# Magnetophon.net
KiCad netlist of a schematic drawn in EAGLE
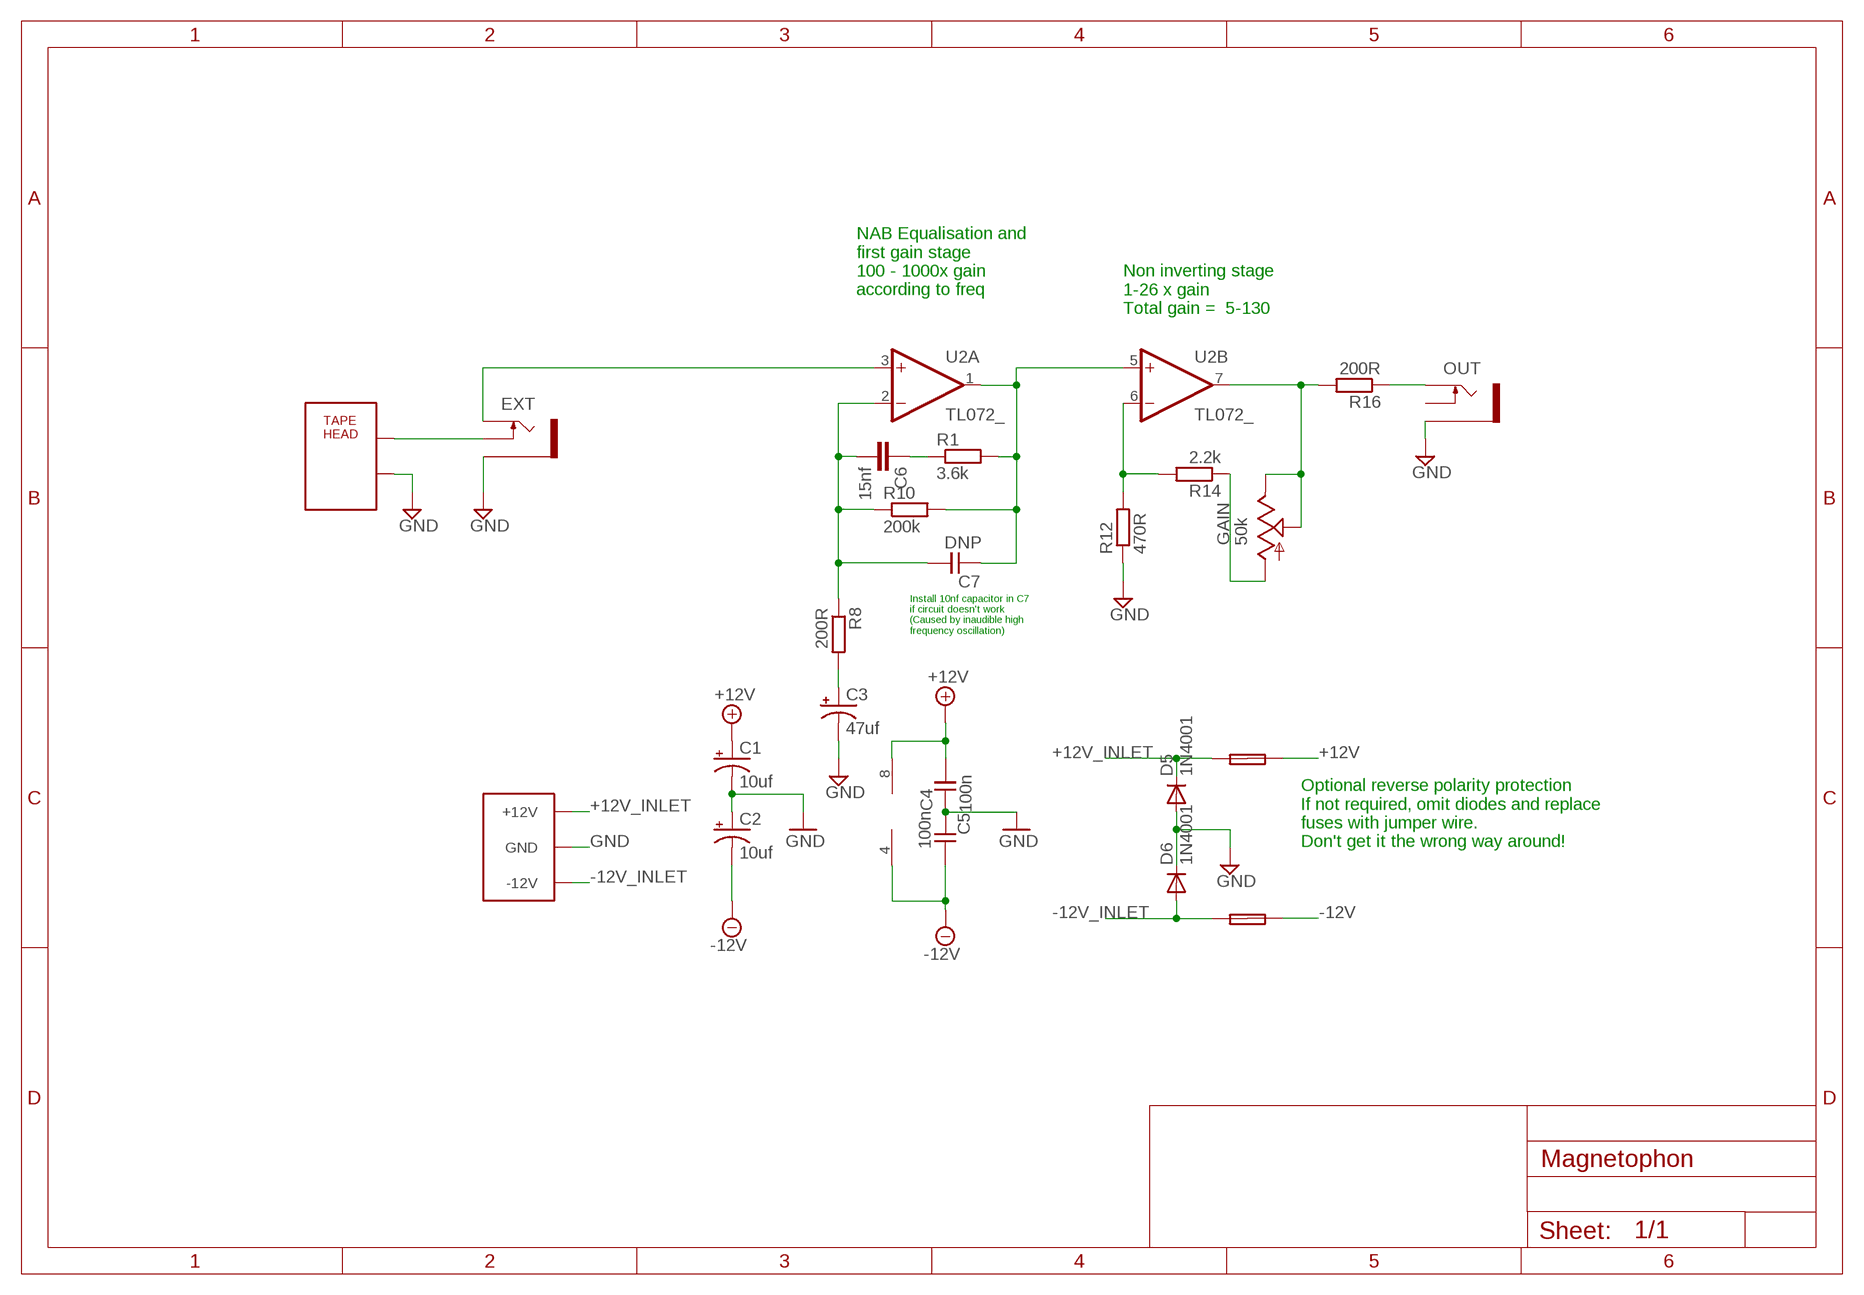
[diagram p0: schematic, sheet 1]

(export (version "E")
  (design (tool "Eeschema 10.0.6"))
  (components
    (comp (ref "1")
      (value "FUSE")
      (footprint "eagle-import:C050H075X075")
      (libsource (lib "eagle-import") (part "PTC_FUSEPOLY_FUSE"))
    )
    (comp (ref "C1")
      (value "10uf")
      (footprint "eagle-import:CPOL-RADIAL-10UF-25V")
      (libsource (lib "eagle-import") (part "CAP_POLPTH2"))
    )
    (comp (ref "C2")
      (value "10uf")
      (footprint "eagle-import:CPOL-RADIAL-10UF-25V")
      (libsource (lib "eagle-import") (part "CAP_POLPTH2"))
    )
    (comp (ref "C3")
      (value "47uf")
      (footprint "eagle-import:CPOL-RADIAL-10UF-25V")
      (libsource (lib "eagle-import") (part "CAP_POLPTH2"))
    )
    (comp (ref "C4")
      (value "100n")
      (footprint "eagle-import:C050-024X044")
      (libsource (lib "eagle-import") (part "C-EU050-024X044"))
    )
    (comp (ref "C5")
      (value "100n")
      (footprint "eagle-import:C050-024X044")
      (libsource (lib "eagle-import") (part "C-EU050-024X044"))
    )
    (comp (ref "C6")
      (value "15nf")
      (footprint "eagle-import:C050-030X075")
      (libsource (lib "eagle-import") (part "rcl_C-EU050-030X075"))
    )
    (comp (ref "C7")
      (value "DNP")
      (footprint "eagle-import:C050-024X044")
      (libsource (lib "eagle-import") (part "C-EU050-024X044"))
    )
    (comp (ref "D5")
      (value "1N4001")
      (footprint "eagle-import:DO41-10")
      (libsource (lib "eagle-import") (part "1N4004"))
    )
    (comp (ref "D6")
      (value "1N4001")
      (footprint "eagle-import:DO41-10")
      (libsource (lib "eagle-import") (part "1N4004"))
    )
    (comp (ref "EXT")
      (value "THONKICONNNEW")
      (footprint "eagle-import:WQP-PJ301M-12_JACK")
      (libsource (lib "eagle-import") (part "THONKICONNNEW"))
    )
    (comp (ref "FUSE")
      (value "FUSE")
      (footprint "eagle-import:C050H075X075")
      (libsource (lib "eagle-import") (part "PTC_FUSEPOLY_FUSE"))
    )
    (comp (ref "GAIN")
      (value "50k")
      (footprint "eagle-import:EVUF")
      (libsource (lib "eagle-import") (part "ALPHA-9MMAF2"))
    )
    (comp (ref "OUT")
      (value "THONKICONNNEW")
      (footprint "eagle-import:WQP-PJ301M-12_JACK")
      (libsource (lib "eagle-import") (part "THONKICONNNEW"))
    )
    (comp (ref "R1")
      (value "3.6k")
      (footprint "eagle-import:7MM_RESISTOR")
      (libsource (lib "eagle-import") (part "RESISTOR7MM"))
    )
    (comp (ref "R8")
      (value "200R")
      (footprint "eagle-import:7MM_RESISTOR")
      (libsource (lib "eagle-import") (part "RESISTOR7MM"))
    )
    (comp (ref "R10")
      (value "200k")
      (footprint "eagle-import:7MM_RESISTOR")
      (libsource (lib "eagle-import") (part "RESISTOR7MM"))
    )
    (comp (ref "R12")
      (value "470R")
      (footprint "eagle-import:7MM_RESISTOR")
      (libsource (lib "eagle-import") (part "RESISTOR7MM"))
    )
    (comp (ref "R14")
      (value "2.2k")
      (footprint "eagle-import:7MM_RESISTOR")
      (libsource (lib "eagle-import") (part "RESISTOR7MM"))
    )
    (comp (ref "R16")
      (value "200R")
      (footprint "eagle-import:7MM_RESISTOR")
      (libsource (lib "eagle-import") (part "RESISTOR7MM"))
    )
    (comp (ref "U$1")
      (value "MONO_CASSETTE_HEAD")
      (footprint "eagle-import:MONO_CASSETTE_HEAD")
      (libsource (lib "eagle-import") (part "MONO_CASSETTE_HEAD"))
    )
    (comp (ref "U$2")
      (value "EURO_POWER_LOCK")
      (footprint "eagle-import:EURO_PWR_HEADER_LOCK")
      (libsource (lib "eagle-import") (part "EURO_POWER_LOCK"))
    )
    (comp (ref "U2")
      (value "TL072_")
      (footprint "eagle-import:DIL08")
      (libsource (lib "eagle-import") (part "TL072_"))
    )
  )
  (nets
    (net (code "1") (name "+12V") (class "Default")
      (node (ref "1") (pin "2") (pinfunction "P$2_2") (pintype "bidirectional"))
      (node (ref "C1") (pin "1") (pinfunction "+_1") (pintype "passive"))
      (node (ref "C4") (pin "1") (pinfunction "1_1") (pintype "passive"))
      (node (ref "U2") (pin "8") (pinfunction "V+_8") (pintype "power_in"))
    )
    (net (code "2") (name "-12V") (class "Default")
      (node (ref "C2") (pin "2") (pinfunction "-_2") (pintype "passive"))
      (node (ref "C5") (pin "1") (pinfunction "1_1") (pintype "passive"))
      (node (ref "FUSE") (pin "2") (pinfunction "P$2_2") (pintype "bidirectional"))
      (node (ref "U2") (pin "4") (pinfunction "V-_4") (pintype "power_in"))
    )
    (net (code "3") (name "/+12V_INLET") (class "Default")
      (node (ref "1") (pin "1") (pinfunction "P$1_1") (pintype "bidirectional"))
      (node (ref "D5") (pin "C") (pinfunction "C_C") (pintype "passive"))
      (node (ref "U$2") (pin "POS1") (pinfunction "+12V_POS1") (pintype "bidirectional"))
      (node (ref "U$2") (pin "POS2") (pinfunction "+12V_POS2") (pintype "bidirectional"))
    )
    (net (code "4") (name "/-12V_INLET") (class "Default")
      (node (ref "D6") (pin "A") (pinfunction "A_A") (pintype "passive"))
      (node (ref "FUSE") (pin "1") (pinfunction "P$1_1") (pintype "bidirectional"))
      (node (ref "U$2") (pin "NEG1") (pinfunction "-12V_NEG1") (pintype "bidirectional"))
      (node (ref "U$2") (pin "NEG2") (pinfunction "-12V_NEG2") (pintype "bidirectional"))
    )
    (net (code "5") (name "GND") (class "Default")
      (node (ref "C1") (pin "2") (pinfunction "-_2") (pintype "passive"))
      (node (ref "C2") (pin "1") (pinfunction "+_1") (pintype "passive"))
      (node (ref "C3") (pin "2") (pinfunction "-_2") (pintype "passive"))
      (node (ref "C4") (pin "2") (pinfunction "2_2") (pintype "passive"))
      (node (ref "C5") (pin "2") (pinfunction "2_2") (pintype "passive"))
      (node (ref "D5") (pin "A") (pinfunction "A_A") (pintype "passive"))
      (node (ref "D6") (pin "C") (pinfunction "C_C") (pintype "passive"))
      (node (ref "EXT") (pin "P$3_SLEEVE") (pinfunction "SLEEVE_P$3_SLEEVE") (pintype "passive"))
      (node (ref "OUT") (pin "P$3_SLEEVE") (pinfunction "SLEEVE_P$3_SLEEVE") (pintype "passive"))
      (node (ref "R12") (pin "1") (pinfunction "1_1") (pintype "passive"))
      (node (ref "U$1") (pin "P$2") (pinfunction "P$2_P$2") (pintype "bidirectional"))
      (node (ref "U$2") (pin "GND1") (pinfunction "GND_GND1") (pintype "bidirectional"))
      (node (ref "U$2") (pin "GND2") (pinfunction "GND_GND2") (pintype "bidirectional"))
      (node (ref "U$2") (pin "GND3") (pinfunction "GND_GND3") (pintype "bidirectional"))
      (node (ref "U$2") (pin "GND4") (pinfunction "GND_GND4") (pintype "bidirectional"))
      (node (ref "U$2") (pin "GND5") (pinfunction "GND_GND5") (pintype "bidirectional"))
      (node (ref "U$2") (pin "GND6") (pinfunction "GND_GND6") (pintype "bidirectional"))
    )
    (net (code "6") (name "Net-(C3-+)") (class "Default")
      (node (ref "C3") (pin "1") (pinfunction "+_1") (pintype "passive"))
      (node (ref "R8") (pin "2") (pinfunction "2_2") (pintype "passive"))
    )
    (net (code "7") (name "Net-(C6-Pad1)") (class "Default")
      (node (ref "C6") (pin "1") (pinfunction "1_1") (pintype "passive"))
      (node (ref "R1") (pin "1") (pinfunction "1_1") (pintype "passive"))
    )
    (net (code "8") (name "Net-(EXT-SWITCH)") (class "Default")
      (node (ref "EXT") (pin "P$2_SWITCH") (pinfunction "SWITCH_P$2_SWITCH") (pintype "passive"))
      (node (ref "U$1") (pin "P$1") (pinfunction "P$1_P$1") (pintype "bidirectional"))
    )
    (net (code "9") (name "Net-(EXT-TIP)") (class "Default")
      (node (ref "EXT") (pin "P$1_TIP") (pinfunction "TIP_P$1_TIP") (pintype "passive"))
      (node (ref "U2") (pin "3") (pinfunction "+IN_3") (pintype "input"))
    )
    (net (code "10") (name "Net-(GAIN-A)") (class "Default")
      (node (ref "GAIN") (pin "1") (pinfunction "A_1") (pintype "passive"))
      (node (ref "R14") (pin "1") (pinfunction "1_1") (pintype "passive"))
    )
    (net (code "11") (name "Net-(GAIN-E)") (class "Default")
      (node (ref "GAIN") (pin "2") (pinfunction "S_2") (pintype "passive"))
      (node (ref "GAIN") (pin "3") (pinfunction "E_3") (pintype "passive"))
      (node (ref "R16") (pin "2") (pinfunction "2_2") (pintype "passive"))
      (node (ref "U2") (pin "7") (pinfunction "OUT_7") (pintype "output"))
    )
    (net (code "12") (name "Net-(OUT-TIP)") (class "Default")
      (node (ref "OUT") (pin "P$1_TIP") (pinfunction "TIP_P$1_TIP") (pintype "passive"))
      (node (ref "R16") (pin "1") (pinfunction "1_1") (pintype "passive"))
    )
    (net (code "13") (name "Net-(U2A--IN)") (class "Default")
      (node (ref "C6") (pin "2") (pinfunction "2_2") (pintype "passive"))
      (node (ref "C7") (pin "1") (pinfunction "1_1") (pintype "passive"))
      (node (ref "R10") (pin "1") (pinfunction "1_1") (pintype "passive"))
      (node (ref "R8") (pin "1") (pinfunction "1_1") (pintype "passive"))
      (node (ref "U2") (pin "2") (pinfunction "-IN_2") (pintype "input"))
    )
    (net (code "14") (name "Net-(U2A-OUT)") (class "Default")
      (node (ref "C7") (pin "2") (pinfunction "2_2") (pintype "passive"))
      (node (ref "R1") (pin "2") (pinfunction "2_2") (pintype "passive"))
      (node (ref "R10") (pin "2") (pinfunction "2_2") (pintype "passive"))
      (node (ref "U2") (pin "1") (pinfunction "OUT_1") (pintype "output"))
      (node (ref "U2") (pin "5") (pinfunction "+IN_5") (pintype "input"))
    )
    (net (code "15") (name "Net-(U2B--IN)") (class "Default")
      (node (ref "R12") (pin "2") (pinfunction "2_2") (pintype "passive"))
      (node (ref "R14") (pin "2") (pinfunction "2_2") (pintype "passive"))
      (node (ref "U2") (pin "6") (pinfunction "-IN_6") (pintype "input"))
    )
    (net (code "16") (name "unconnected-(OUT-SWITCH-PadP$2_SWITCH)") (class "Default")
      (node (ref "OUT") (pin "P$2_SWITCH") (pinfunction "SWITCH_P$2_SWITCH") (pintype "passive"))
    )
  )
)
